# SuperSensors_DIP.net
KiCad netlist of a schematic drawn in EAGLE
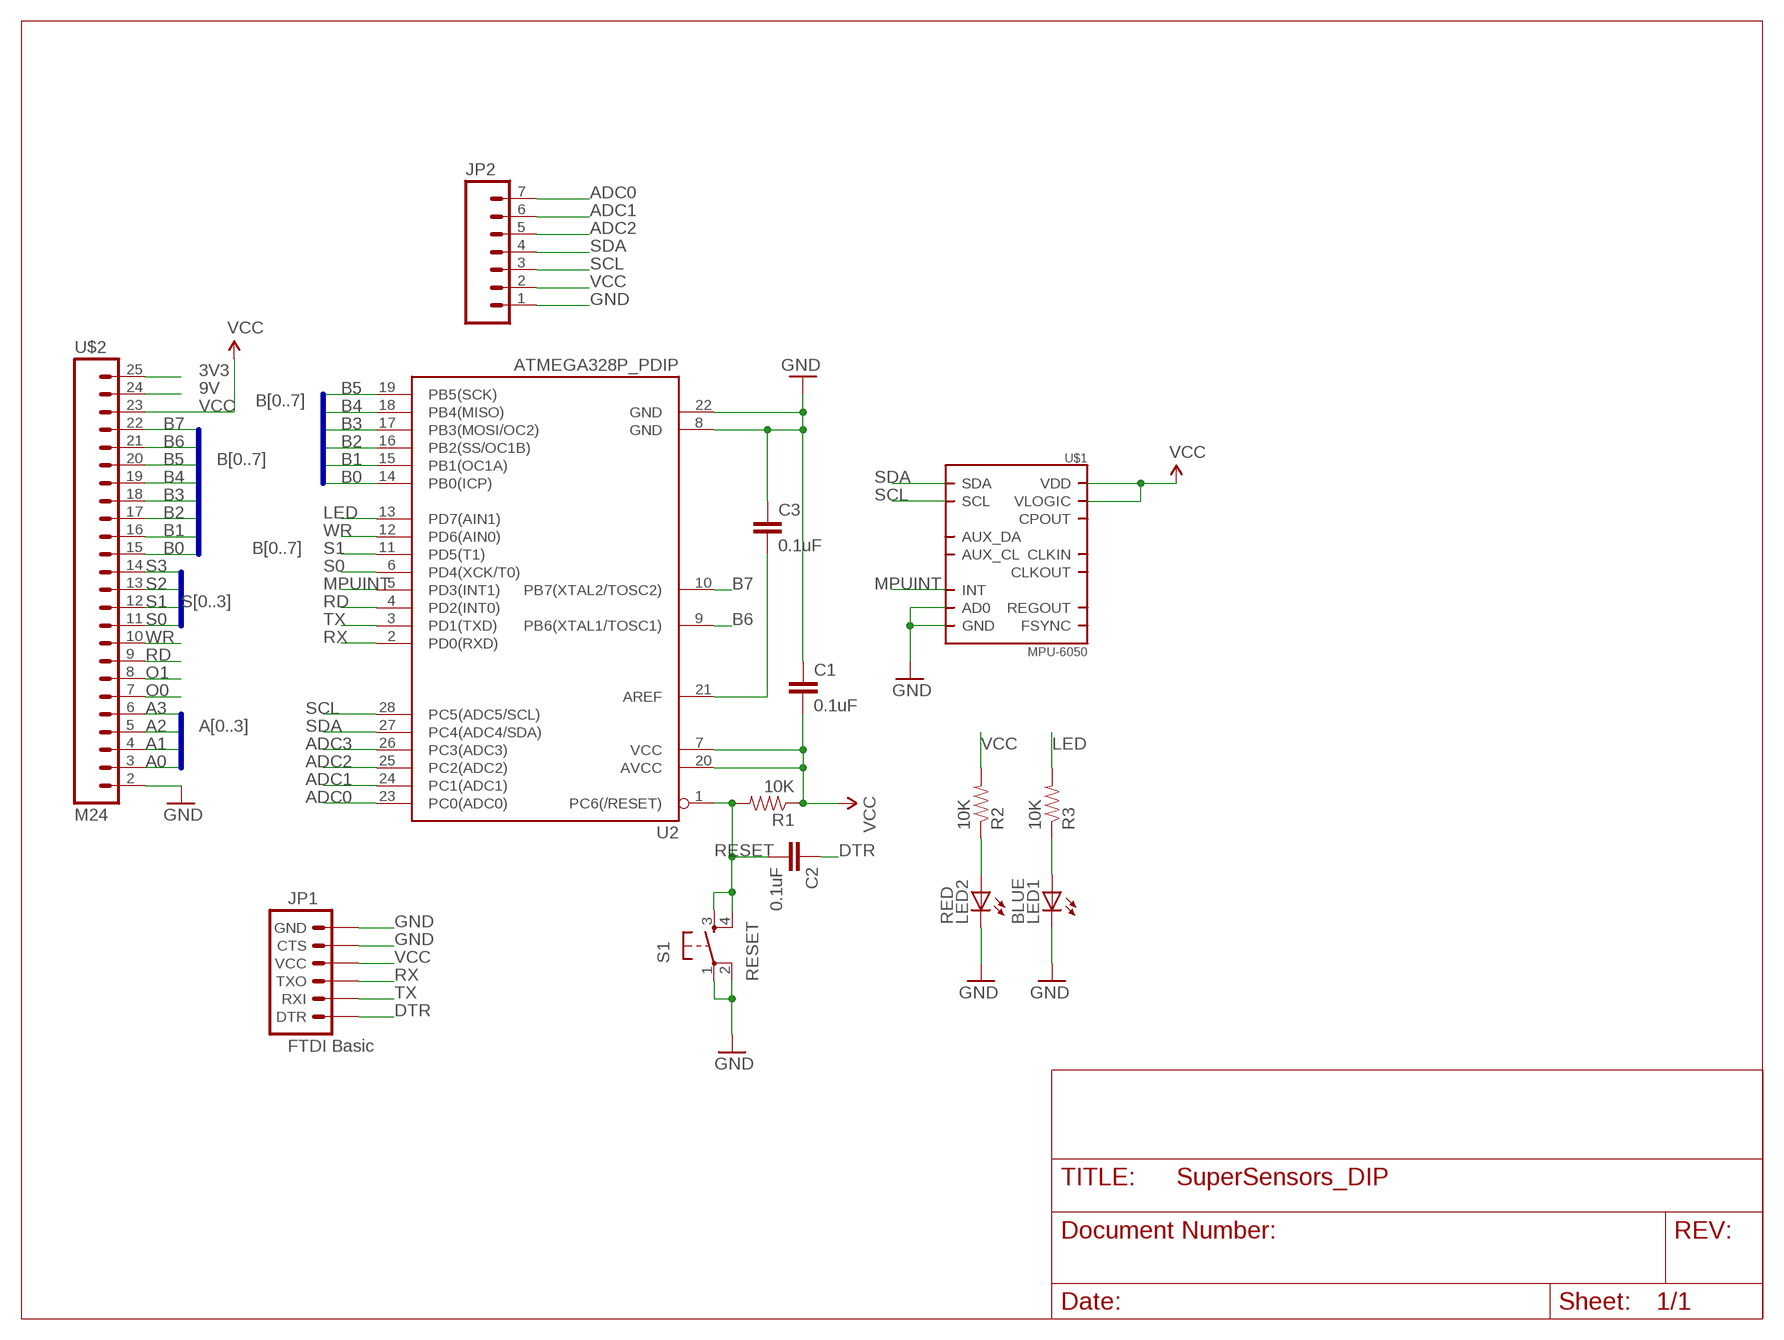
[diagram p0: schematic, sheet 1]

(export (version "E")
  (design (tool "Eeschema 10.0.6"))
  (components
    (comp (ref "C1")
      (value "0.1uF")
      (footprint "eagle-import:CAP-PTH-SMALL")
      (libsource (lib "eagle-import") (part "CAPPTH"))
    )
    (comp (ref "C2")
      (value "0.1uF")
      (footprint "eagle-import:CAP-PTH-SMALL")
      (libsource (lib "eagle-import") (part "CAPPTH"))
    )
    (comp (ref "C3")
      (value "0.1uF")
      (footprint "eagle-import:CAP-PTH-SMALL")
      (libsource (lib "eagle-import") (part "CAPPTH"))
    )
    (comp (ref "JP1")
      (value "FTDI Basic")
      (footprint "eagle-import:1X06")
      (libsource (lib "eagle-import") (part "ARDUINO_SERIAL_PROGRAMPTH"))
    )
    (comp (ref "JP2")
      (value "M07")
      (footprint "eagle-import:1X07")
      (libsource (lib "eagle-import") (part "M07"))
    )
    (comp (ref "LED1")
      (value "BLUE")
      (footprint "eagle-import:LED5MM")
      (libsource (lib "eagle-import") (part "LED5MM"))
    )
    (comp (ref "LED2")
      (value "RED")
      (footprint "eagle-import:LED5MM")
      (libsource (lib "eagle-import") (part "LED5MM"))
    )
    (comp (ref "R1")
      (value "10K")
      (footprint "eagle-import:AXIAL-0.4")
      (libsource (lib "eagle-import") (part "RESISTORPTH-1/4W"))
    )
    (comp (ref "R2")
      (value "10K")
      (footprint "eagle-import:AXIAL-0.4")
      (libsource (lib "eagle-import") (part "RESISTORPTH-1/4W"))
    )
    (comp (ref "R3")
      (value "10K")
      (footprint "eagle-import:AXIAL-0.4")
      (libsource (lib "eagle-import") (part "RESISTORPTH-1/4W"))
    )
    (comp (ref "S1")
      (value "RESET")
      (footprint "eagle-import:TACTILE_SWITCH_SMD")
      (libsource (lib "eagle-import") (part "TAC_SWITCHSMD"))
    )
    (comp (ref "U$1")
      (value "MPU-6050")
      (footprint "eagle-import:QFN.24.4X4")
      (libsource (lib "eagle-import") (part "MPU-6050"))
    )
    (comp (ref "U$2")
      (value "M24")
      (footprint "eagle-import:1X24")
      (libsource (lib "eagle-import") (part "M24"))
    )
    (comp (ref "U2")
      (value "ATMEGA328P_PDIP")
      (footprint "eagle-import:DIL28-3")
      (libsource (lib "eagle-import") (part "ATMEGA328P_PDIP"))
    )
  )
  (nets
    (net (code "1") (name "/3V3") (class "Default")
      (node (ref "U$2") (pin "25") (pinfunction "25_25") (pintype "passive"))
    )
    (net (code "2") (name "/9V") (class "Default")
      (node (ref "U$2") (pin "24") (pinfunction "24_24") (pintype "passive"))
    )
    (net (code "3") (name "/A0") (class "Default")
      (node (ref "U$2") (pin "3") (pinfunction "3_3") (pintype "passive"))
    )
    (net (code "4") (name "/A1") (class "Default")
      (node (ref "U$2") (pin "4") (pinfunction "4_4") (pintype "passive"))
    )
    (net (code "5") (name "/A2") (class "Default")
      (node (ref "U$2") (pin "5") (pinfunction "5_5") (pintype "passive"))
    )
    (net (code "6") (name "/A3") (class "Default")
      (node (ref "U$2") (pin "6") (pinfunction "6_6") (pintype "passive"))
    )
    (net (code "7") (name "/ADC0") (class "Default")
      (node (ref "JP2") (pin "7") (pinfunction "7_7") (pintype "passive"))
      (node (ref "U2") (pin "23") (pinfunction "PC0(ADC0)_23") (pintype "bidirectional"))
    )
    (net (code "8") (name "/ADC1") (class "Default")
      (node (ref "JP2") (pin "6") (pinfunction "6_6") (pintype "passive"))
      (node (ref "U2") (pin "24") (pinfunction "PC1(ADC1)_24") (pintype "bidirectional"))
    )
    (net (code "9") (name "/ADC2") (class "Default")
      (node (ref "JP2") (pin "5") (pinfunction "5_5") (pintype "passive"))
      (node (ref "U2") (pin "25") (pinfunction "PC2(ADC2)_25") (pintype "bidirectional"))
    )
    (net (code "10") (name "/ADC3") (class "Default")
      (node (ref "U2") (pin "26") (pinfunction "PC3(ADC3)_26") (pintype "bidirectional"))
    )
    (net (code "12") (name "/B0") (class "Default")
      (node (ref "U$2") (pin "15") (pinfunction "15_15") (pintype "passive"))
      (node (ref "U2") (pin "14") (pinfunction "PB0(ICP)_14") (pintype "bidirectional"))
    )
    (net (code "13") (name "/B1") (class "Default")
      (node (ref "U$2") (pin "16") (pinfunction "16_16") (pintype "passive"))
      (node (ref "U2") (pin "15") (pinfunction "PB1(OC1A)_15") (pintype "bidirectional"))
    )
    (net (code "14") (name "/B2") (class "Default")
      (node (ref "U$2") (pin "17") (pinfunction "17_17") (pintype "passive"))
      (node (ref "U2") (pin "16") (pinfunction "PB2(SS/OC1B)_16") (pintype "bidirectional"))
    )
    (net (code "15") (name "/B3") (class "Default")
      (node (ref "U$2") (pin "18") (pinfunction "18_18") (pintype "passive"))
      (node (ref "U2") (pin "17") (pinfunction "PB3(MOSI/OC2)_17") (pintype "bidirectional"))
    )
    (net (code "16") (name "/B4") (class "Default")
      (node (ref "U$2") (pin "19") (pinfunction "19_19") (pintype "passive"))
      (node (ref "U2") (pin "18") (pinfunction "PB4(MISO)_18") (pintype "bidirectional"))
    )
    (net (code "17") (name "/B5") (class "Default")
      (node (ref "U$2") (pin "20") (pinfunction "20_20") (pintype "passive"))
      (node (ref "U2") (pin "19") (pinfunction "PB5(SCK)_19") (pintype "bidirectional"))
    )
    (net (code "18") (name "/B6") (class "Default")
      (node (ref "U$2") (pin "21") (pinfunction "21_21") (pintype "passive"))
      (node (ref "U2") (pin "9") (pinfunction "PB6(XTAL1/TOSC1)_9") (pintype "bidirectional"))
    )
    (net (code "19") (name "/B7") (class "Default")
      (node (ref "U$2") (pin "22") (pinfunction "22_22") (pintype "passive"))
      (node (ref "U2") (pin "10") (pinfunction "PB7(XTAL2/TOSC2)_10") (pintype "bidirectional"))
    )
    (net (code "21") (name "/DTR") (class "Default")
      (node (ref "C2") (pin "1") (pinfunction "1_1") (pintype "passive"))
      (node (ref "JP1") (pin "1") (pinfunction "DTR_1") (pintype "passive"))
    )
    (net (code "22") (name "/LED") (class "Default")
      (node (ref "R3") (pin "P$2") (pinfunction "2_P$2") (pintype "passive"))
      (node (ref "U2") (pin "13") (pinfunction "PD7(AIN1)_13") (pintype "bidirectional"))
    )
    (net (code "23") (name "/MPUINT") (class "Default")
      (node (ref "U$1") (pin "12") (pinfunction "INT_12") (pintype "bidirectional"))
      (node (ref "U2") (pin "5") (pinfunction "PD3(INT1)_5") (pintype "bidirectional"))
    )
    (net (code "24") (name "/O0") (class "Default")
      (node (ref "U$2") (pin "7") (pinfunction "7_7") (pintype "passive"))
    )
    (net (code "25") (name "/O1") (class "Default")
      (node (ref "U$2") (pin "8") (pinfunction "8_8") (pintype "passive"))
    )
    (net (code "26") (name "/RD") (class "Default")
      (node (ref "U$2") (pin "9") (pinfunction "9_9") (pintype "passive"))
      (node (ref "U2") (pin "4") (pinfunction "PD2(INT0)_4") (pintype "bidirectional"))
    )
    (net (code "27") (name "/RESET") (class "Default")
      (node (ref "C2") (pin "2") (pinfunction "2_2") (pintype "passive"))
      (node (ref "R1") (pin "P$2") (pinfunction "2_P$2") (pintype "passive"))
      (node (ref "S1") (pin "3") (pinfunction "3_3") (pintype "passive"))
      (node (ref "S1") (pin "4") (pinfunction "4_4") (pintype "passive"))
      (node (ref "U2") (pin "1") (pinfunction "PC6(/RESET)_1") (pintype "bidirectional"))
    )
    (net (code "28") (name "/RX") (class "Default")
      (node (ref "JP1") (pin "3") (pinfunction "TXO_3") (pintype "passive"))
      (node (ref "U2") (pin "2") (pinfunction "PD0(RXD)_2") (pintype "bidirectional"))
    )
    (net (code "29") (name "/S0") (class "Default")
      (node (ref "U$2") (pin "11") (pinfunction "11_11") (pintype "passive"))
      (node (ref "U2") (pin "6") (pinfunction "PD4(XCK/T0)_6") (pintype "bidirectional"))
    )
    (net (code "30") (name "/S1") (class "Default")
      (node (ref "U$2") (pin "12") (pinfunction "12_12") (pintype "passive"))
      (node (ref "U2") (pin "11") (pinfunction "PD5(T1)_11") (pintype "bidirectional"))
    )
    (net (code "31") (name "/S2") (class "Default")
      (node (ref "U$2") (pin "13") (pinfunction "13_13") (pintype "passive"))
    )
    (net (code "32") (name "/S3") (class "Default")
      (node (ref "U$2") (pin "14") (pinfunction "14_14") (pintype "passive"))
    )
    (net (code "33") (name "/SCL") (class "Default")
      (node (ref "JP2") (pin "3") (pinfunction "3_3") (pintype "passive"))
      (node (ref "U$1") (pin "23") (pinfunction "SCL_23") (pintype "bidirectional"))
      (node (ref "U2") (pin "28") (pinfunction "PC5(ADC5/SCL)_28") (pintype "bidirectional"))
    )
    (net (code "34") (name "/SDA") (class "Default")
      (node (ref "JP2") (pin "4") (pinfunction "4_4") (pintype "passive"))
      (node (ref "U$1") (pin "24") (pinfunction "SDA_24") (pintype "bidirectional"))
      (node (ref "U2") (pin "27") (pinfunction "PC4(ADC4/SDA)_27") (pintype "bidirectional"))
    )
    (net (code "36") (name "/TX") (class "Default")
      (node (ref "JP1") (pin "2") (pinfunction "RXI_2") (pintype "passive"))
      (node (ref "U2") (pin "3") (pinfunction "PD1(TXD)_3") (pintype "bidirectional"))
    )
    (net (code "37") (name "/WR") (class "Default")
      (node (ref "U$2") (pin "10") (pinfunction "10_10") (pintype "passive"))
      (node (ref "U2") (pin "12") (pinfunction "PD6(AIN0)_12") (pintype "bidirectional"))
    )
    (net (code "38") (name "GND") (class "Default")
      (node (ref "C1") (pin "1") (pinfunction "1_1") (pintype "passive"))
      (node (ref "C3") (pin "1") (pinfunction "1_1") (pintype "passive"))
      (node (ref "JP1") (pin "5") (pinfunction "CTS_5") (pintype "passive"))
      (node (ref "JP1") (pin "6") (pinfunction "GND_6") (pintype "passive"))
      (node (ref "JP2") (pin "1") (pinfunction "1_1") (pintype "passive"))
      (node (ref "LED1") (pin "K") (pinfunction "C_K") (pintype "passive"))
      (node (ref "LED2") (pin "K") (pinfunction "C_K") (pintype "passive"))
      (node (ref "S1") (pin "1") (pinfunction "1_1") (pintype "passive"))
      (node (ref "S1") (pin "2") (pinfunction "2_2") (pintype "passive"))
      (node (ref "U$1") (pin "18") (pinfunction "GND_18") (pintype "bidirectional"))
      (node (ref "U$1") (pin "9") (pinfunction "AD0_9") (pintype "bidirectional"))
      (node (ref "U$2") (pin "2") (pinfunction "2_2") (pintype "passive"))
      (node (ref "U2") (pin "22") (pinfunction "GND_22") (pintype "bidirectional"))
      (node (ref "U2") (pin "8") (pinfunction "GND_8") (pintype "bidirectional"))
    )
    (net (code "39") (name "Net-(R2-1)") (class "Default")
      (node (ref "LED2") (pin "A") (pinfunction "A_A") (pintype "passive"))
      (node (ref "R2") (pin "P$1") (pinfunction "1_P$1") (pintype "passive"))
    )
    (net (code "40") (name "Net-(R3-1)") (class "Default")
      (node (ref "LED1") (pin "A") (pinfunction "A_A") (pintype "passive"))
      (node (ref "R3") (pin "P$1") (pinfunction "1_P$1") (pintype "passive"))
    )
    (net (code "41") (name "Net-(U2-AREF)") (class "Default")
      (node (ref "C3") (pin "2") (pinfunction "2_2") (pintype "passive"))
      (node (ref "U2") (pin "21") (pinfunction "AREF_21") (pintype "bidirectional"))
    )
    (net (code "42") (name "VCC") (class "Default")
      (node (ref "C1") (pin "2") (pinfunction "2_2") (pintype "passive"))
      (node (ref "JP1") (pin "4") (pinfunction "VCC_4") (pintype "passive"))
      (node (ref "JP2") (pin "2") (pinfunction "2_2") (pintype "passive"))
      (node (ref "R1") (pin "P$1") (pinfunction "1_P$1") (pintype "passive"))
      (node (ref "R2") (pin "P$2") (pinfunction "2_P$2") (pintype "passive"))
      (node (ref "U$1") (pin "13") (pinfunction "VDD_13") (pintype "bidirectional"))
      (node (ref "U$1") (pin "8") (pinfunction "VLOGIC_8") (pintype "bidirectional"))
      (node (ref "U$2") (pin "23") (pinfunction "23_23") (pintype "passive"))
      (node (ref "U2") (pin "20") (pinfunction "AVCC_20") (pintype "bidirectional"))
      (node (ref "U2") (pin "7") (pinfunction "VCC_7") (pintype "bidirectional"))
    )
    (net (code "43") (name "unconnected-(U$1-AUX_CL-Pad7)") (class "Default")
      (node (ref "U$1") (pin "7") (pinfunction "AUX_CL_7") (pintype "bidirectional"))
    )
    (net (code "44") (name "unconnected-(U$1-AUX_DA-Pad6)") (class "Default")
      (node (ref "U$1") (pin "6") (pinfunction "AUX_DA_6") (pintype "bidirectional"))
    )
    (net (code "45") (name "unconnected-(U$1-CLKIN-Pad1)") (class "Default")
      (node (ref "U$1") (pin "1") (pinfunction "CLKIN_1") (pintype "bidirectional"))
    )
    (net (code "46") (name "unconnected-(U$1-CLKOUT-Pad22)") (class "Default")
      (node (ref "U$1") (pin "22") (pinfunction "CLKOUT_22") (pintype "bidirectional"))
    )
    (net (code "47") (name "unconnected-(U$1-CPOUT-Pad20)") (class "Default")
      (node (ref "U$1") (pin "20") (pinfunction "CPOUT_20") (pintype "bidirectional"))
    )
    (net (code "48") (name "unconnected-(U$1-FSYNC-Pad11)") (class "Default")
      (node (ref "U$1") (pin "11") (pinfunction "FSYNC_11") (pintype "bidirectional"))
    )
    (net (code "49") (name "unconnected-(U$1-REGOUT-Pad10)") (class "Default")
      (node (ref "U$1") (pin "10") (pinfunction "REGOUT_10") (pintype "bidirectional"))
    )
  )
)
